# 08_Extention_GPIO.net
KiCad netlist of a schematic drawn in Altium Designer
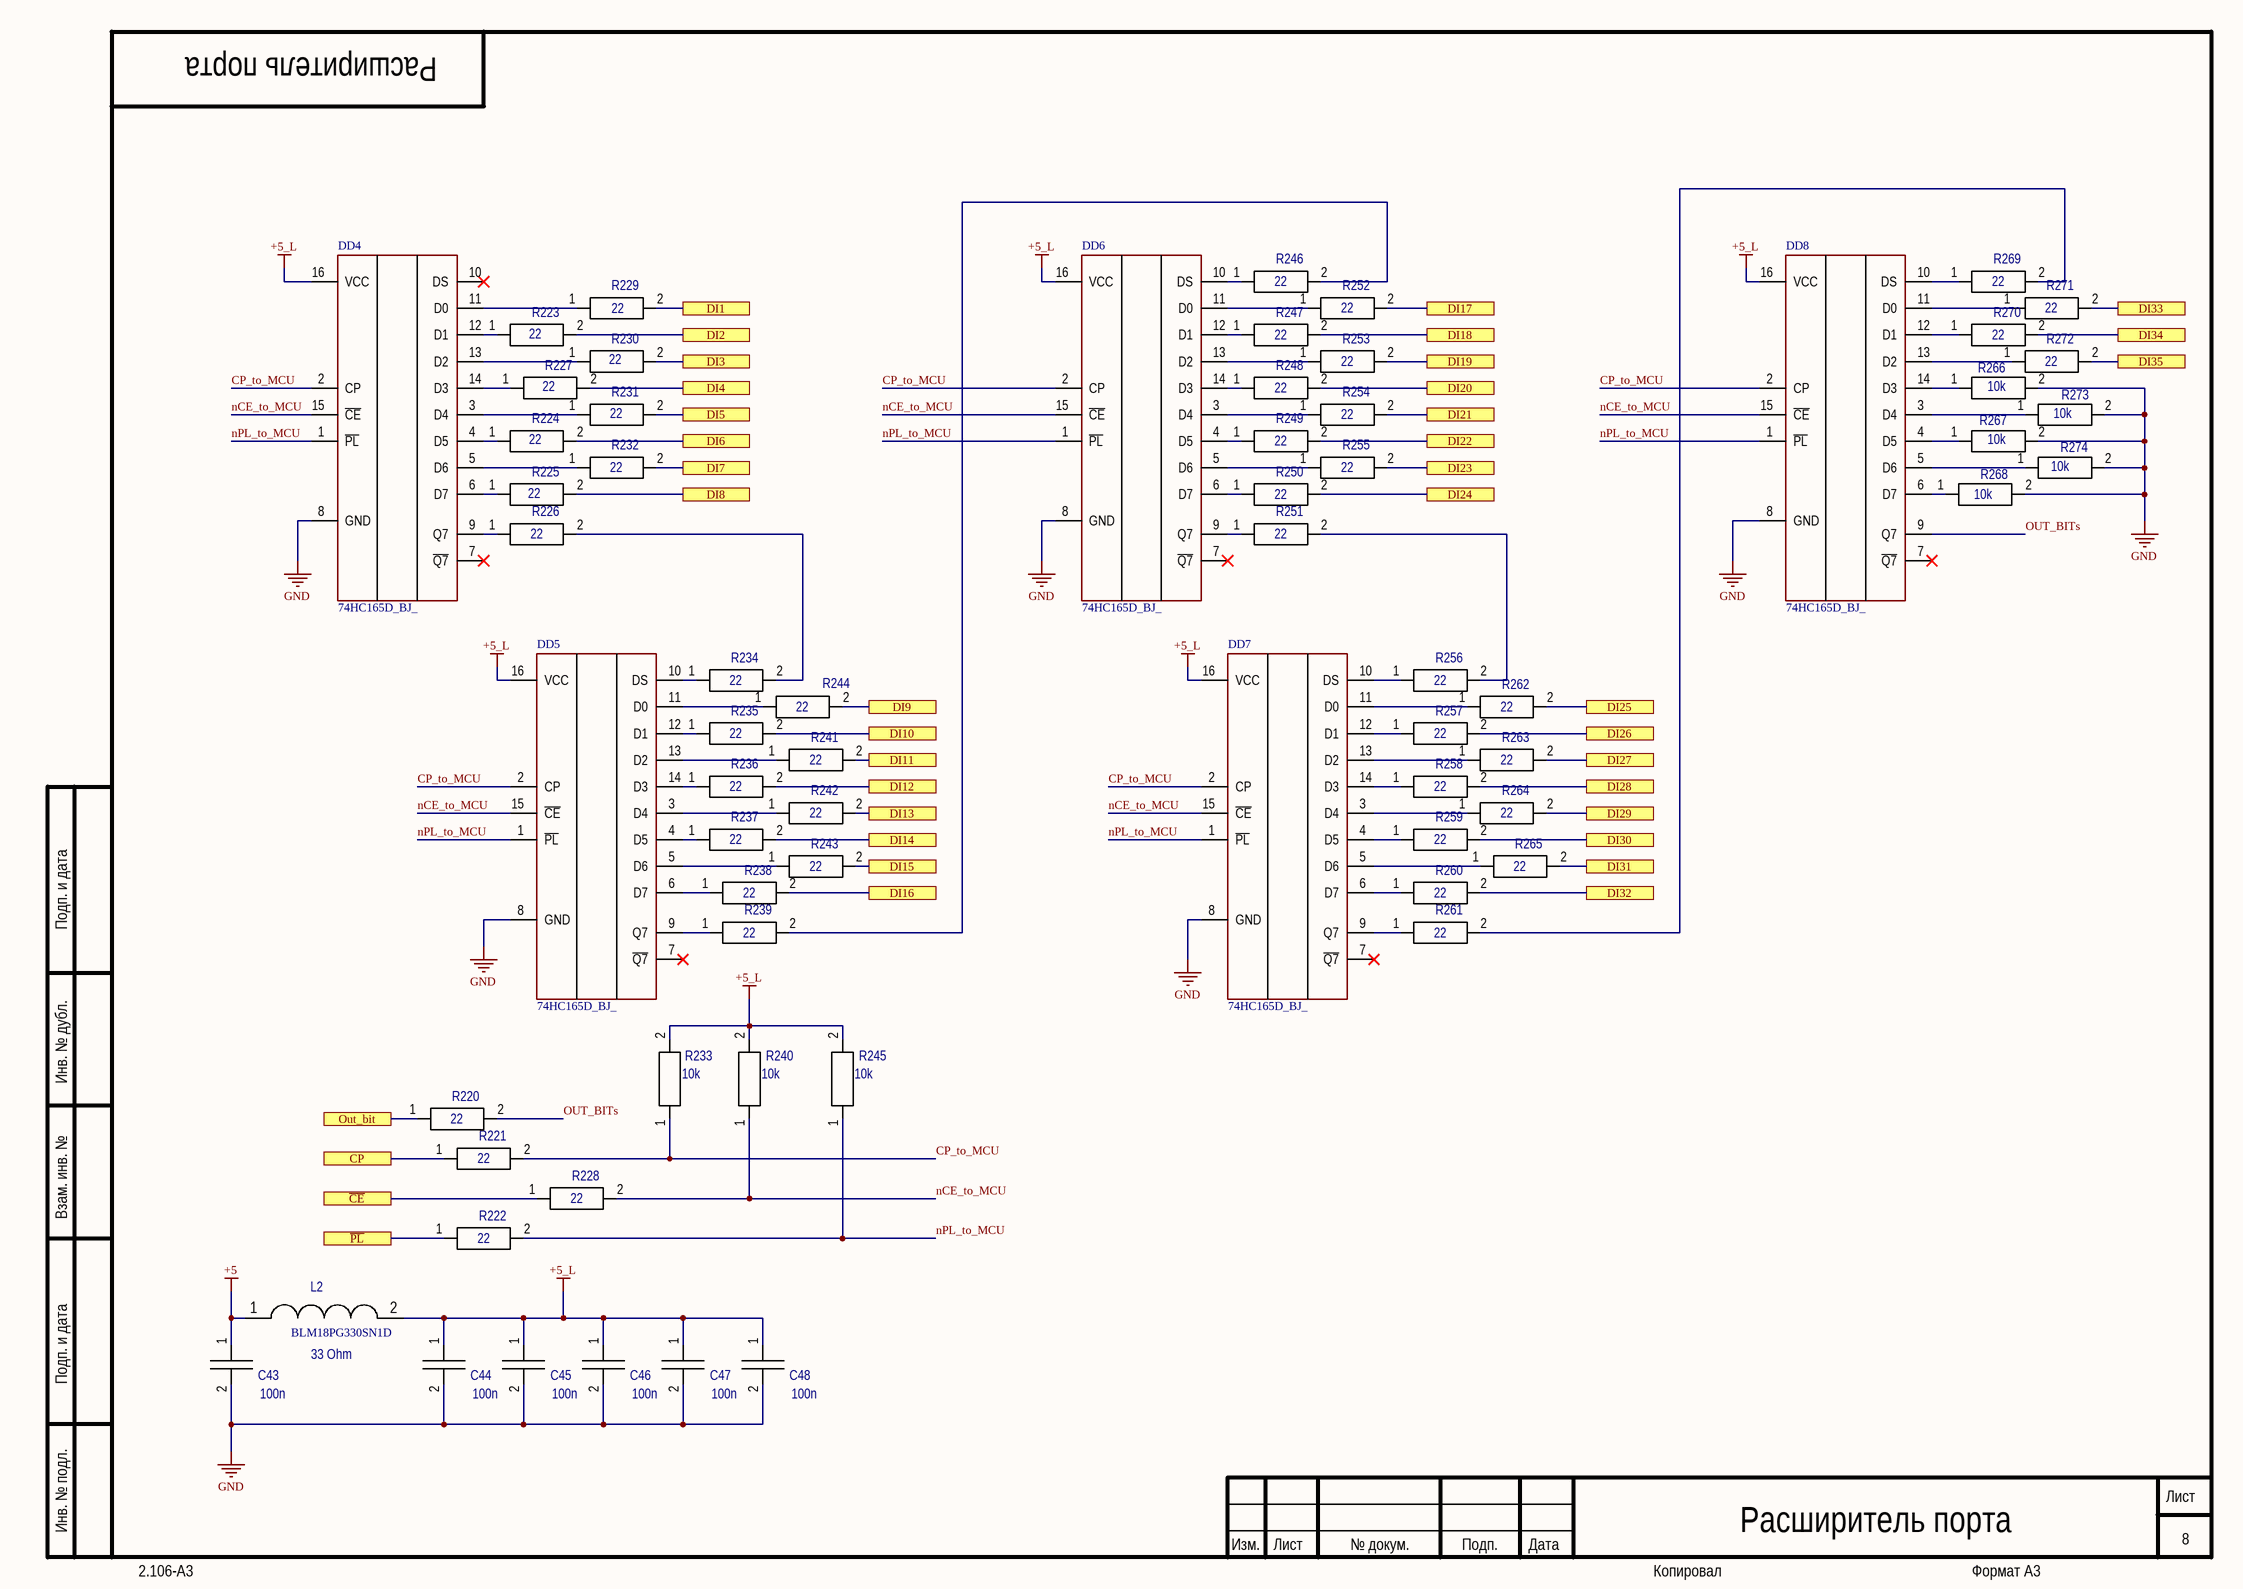
[diagram p0: 08_Extention_GPIO.SchDoc]

(export (version "E")
  (design (tool "Eeschema 10.0.6"))
  (components
    (comp (ref "C43")
      (value "100n")
      (footprint "C0603")
      (fields
        (field (name "PART NUMBER") "GRM188R71C104KA01D")
        (field (name "TOLERANCE") "±10%")
        (field (name "MANUFACTURER") "Murata Manufacturing")
      )
      (libsource (lib "AccessLibrary") (part "Capacitor"))
    )
    (comp (ref "C44")
      (value "100n")
      (footprint "C0603")
      (fields
        (field (name "PART NUMBER") "GRM188R71C104KA01D")
        (field (name "TOLERANCE") "±10%")
        (field (name "MANUFACTURER") "Murata Manufacturing")
      )
      (libsource (lib "AccessLibrary") (part "Capacitor"))
    )
    (comp (ref "C45")
      (value "100n")
      (footprint "C0603")
      (fields
        (field (name "PART NUMBER") "GRM188R71C104KA01D")
        (field (name "TOLERANCE") "±10%")
        (field (name "MANUFACTURER") "Murata Manufacturing")
      )
      (libsource (lib "AccessLibrary") (part "Capacitor"))
    )
    (comp (ref "C46")
      (value "100n")
      (footprint "C0603")
      (fields
        (field (name "PART NUMBER") "GRM188R71C104KA01D")
        (field (name "TOLERANCE") "±10%")
        (field (name "MANUFACTURER") "Murata Manufacturing")
      )
      (libsource (lib "AccessLibrary") (part "Capacitor"))
    )
    (comp (ref "C47")
      (value "100n")
      (footprint "C0603")
      (fields
        (field (name "PART NUMBER") "GRM188R71C104KA01D")
        (field (name "TOLERANCE") "±10%")
        (field (name "MANUFACTURER") "Murata Manufacturing")
      )
      (libsource (lib "AccessLibrary") (part "Capacitor"))
    )
    (comp (ref "C48")
      (value "100n")
      (footprint "C0603")
      (fields
        (field (name "PART NUMBER") "GRM188R71C104KA01D")
        (field (name "TOLERANCE") "±10%")
        (field (name "MANUFACTURER") "Murata Manufacturing")
      )
      (libsource (lib "AccessLibrary") (part "Capacitor"))
    )
    (comp (ref "DD4")
      (value "74HC165D_BJ_")
      (footprint "board:SOIC127P600X175-16N")
      (description "Integrated Circuit")
      (fields (field (name "PARTNUMBER") "74HC165D(BJ)") (field (name "MOUSER PART NUMBER") "757-74HC165DBJ"))
      (libsource (lib "board") (part "74HC165D_BJ_"))
    )
    (comp (ref "DD5")
      (value "74HC165D_BJ_")
      (footprint "board:SOIC127P600X175-16N")
      (description "Integrated Circuit")
      (fields (field (name "PARTNUMBER") "74HC165D(BJ)") (field (name "MOUSER PART NUMBER") "757-74HC165DBJ"))
      (libsource (lib "board") (part "74HC165D_BJ_"))
    )
    (comp (ref "DD6")
      (value "74HC165D_BJ_")
      (footprint "board:SOIC127P600X175-16N")
      (description "Integrated Circuit")
      (fields (field (name "PARTNUMBER") "74HC165D(BJ)") (field (name "MOUSER PART NUMBER") "757-74HC165DBJ"))
      (libsource (lib "board") (part "74HC165D_BJ_"))
    )
    (comp (ref "DD7")
      (value "74HC165D_BJ_")
      (footprint "board:SOIC127P600X175-16N")
      (description "Integrated Circuit")
      (fields (field (name "PARTNUMBER") "74HC165D(BJ)") (field (name "MOUSER PART NUMBER") "757-74HC165DBJ"))
      (libsource (lib "board") (part "74HC165D_BJ_"))
    )
    (comp (ref "DD8")
      (value "74HC165D_BJ_")
      (footprint "board:SOIC127P600X175-16N")
      (description "Integrated Circuit")
      (fields (field (name "PARTNUMBER") "74HC165D(BJ)") (field (name "MOUSER PART NUMBER") "757-74HC165DBJ"))
      (libsource (lib "board") (part "74HC165D_BJ_"))
    )
    (comp (ref "L2")
      (value "BLM18PG330SN1D")
      (footprint "INDC1608N")
      (fields (field (name "ALTIUM_VALUE") "33 Ohm"))
      (libsource (lib "AccessLibrary") (part "Inductance"))
    )
    (comp (ref "R220")
      (value "22")
      (footprint "RESC1608N")
      (fields
        (field (name "PART NUMBER") "RC0603FK-0722RL")
        (field (name "TOLERANCE") "±1%")
        (field (name "MANUFACTURER") "Тайвань")
      )
      (libsource (lib "AccessLibrary") (part "Resistor"))
    )
    (comp (ref "R221")
      (value "22")
      (footprint "RESC1608N")
      (fields
        (field (name "PART NUMBER") "RC0603FK-0722RL")
        (field (name "TOLERANCE") "±1%")
        (field (name "MANUFACTURER") "Тайвань")
      )
      (libsource (lib "AccessLibrary") (part "Resistor"))
    )
    (comp (ref "R222")
      (value "22")
      (footprint "RESC1608N")
      (fields
        (field (name "PART NUMBER") "RC0603FK-0722RL")
        (field (name "TOLERANCE") "±1%")
        (field (name "MANUFACTURER") "Тайвань")
      )
      (libsource (lib "AccessLibrary") (part "Resistor"))
    )
    (comp (ref "R223")
      (value "22")
      (footprint "RESC1608N")
      (fields
        (field (name "PART NUMBER") "RC0603FK-0722RL")
        (field (name "TOLERANCE") "±1%")
        (field (name "MANUFACTURER") "Тайвань")
      )
      (libsource (lib "AccessLibrary") (part "Resistor"))
    )
    (comp (ref "R224")
      (value "22")
      (footprint "RESC1608N")
      (fields
        (field (name "PART NUMBER") "RC0603FK-0722RL")
        (field (name "TOLERANCE") "±1%")
        (field (name "MANUFACTURER") "Тайвань")
      )
      (libsource (lib "AccessLibrary") (part "Resistor"))
    )
    (comp (ref "R225")
      (value "22")
      (footprint "RESC1608N")
      (fields
        (field (name "PART NUMBER") "RC0603FK-0722RL")
        (field (name "TOLERANCE") "±1%")
        (field (name "MANUFACTURER") "Тайвань")
      )
      (libsource (lib "AccessLibrary") (part "Resistor"))
    )
    (comp (ref "R226")
      (value "22")
      (footprint "RESC1608N")
      (fields
        (field (name "PART NUMBER") "RC0603FK-0722RL")
        (field (name "TOLERANCE") "±1%")
        (field (name "MANUFACTURER") "Тайвань")
      )
      (libsource (lib "AccessLibrary") (part "Resistor"))
    )
    (comp (ref "R227")
      (value "22")
      (footprint "RESC1608N")
      (fields
        (field (name "PART NUMBER") "RC0603FK-0722RL")
        (field (name "TOLERANCE") "±1%")
        (field (name "MANUFACTURER") "Тайвань")
      )
      (libsource (lib "AccessLibrary") (part "Resistor"))
    )
    (comp (ref "R228")
      (value "22")
      (footprint "RESC1608N")
      (fields
        (field (name "PART NUMBER") "RC0603FK-0722RL")
        (field (name "TOLERANCE") "±1%")
        (field (name "MANUFACTURER") "Тайвань")
      )
      (libsource (lib "AccessLibrary") (part "Resistor"))
    )
    (comp (ref "R229")
      (value "22")
      (footprint "RESC1608N")
      (fields
        (field (name "PART NUMBER") "RC0603FK-0722RL")
        (field (name "TOLERANCE") "±1%")
        (field (name "MANUFACTURER") "Тайвань")
      )
      (libsource (lib "AccessLibrary") (part "Resistor"))
    )
    (comp (ref "R230")
      (value "22")
      (footprint "RESC1608N")
      (fields
        (field (name "PART NUMBER") "RC0603FK-0722RL")
        (field (name "TOLERANCE") "±1%")
        (field (name "MANUFACTURER") "Тайвань")
      )
      (libsource (lib "AccessLibrary") (part "Resistor"))
    )
    (comp (ref "R231")
      (value "22")
      (footprint "RESC1608N")
      (fields
        (field (name "PART NUMBER") "RC0603FK-0722RL")
        (field (name "TOLERANCE") "±1%")
        (field (name "MANUFACTURER") "Тайвань")
      )
      (libsource (lib "AccessLibrary") (part "Resistor"))
    )
    (comp (ref "R232")
      (value "22")
      (footprint "RESC1608N")
      (fields
        (field (name "PART NUMBER") "RC0603FK-0722RL")
        (field (name "TOLERANCE") "±1%")
        (field (name "MANUFACTURER") "Тайвань")
      )
      (libsource (lib "AccessLibrary") (part "Resistor"))
    )
    (comp (ref "R233")
      (value "10k")
      (footprint "RESC1608N")
      (fields
        (field (name "PART NUMBER") "RC0603FR-0710KL")
        (field (name "TOLERANCE") "±1%")
        (field (name "MANUFACTURER") "Тайвань")
      )
      (libsource (lib "AccessLibrary") (part "Resistor"))
    )
    (comp (ref "R234")
      (value "22")
      (footprint "RESC1608N")
      (fields
        (field (name "PART NUMBER") "RC0603FK-0722RL")
        (field (name "TOLERANCE") "±1%")
        (field (name "MANUFACTURER") "Тайвань")
      )
      (libsource (lib "AccessLibrary") (part "Resistor"))
    )
    (comp (ref "R235")
      (value "22")
      (footprint "RESC1608N")
      (fields
        (field (name "PART NUMBER") "RC0603FK-0722RL")
        (field (name "TOLERANCE") "±1%")
        (field (name "MANUFACTURER") "Тайвань")
      )
      (libsource (lib "AccessLibrary") (part "Resistor"))
    )
    (comp (ref "R236")
      (value "22")
      (footprint "RESC1608N")
      (fields
        (field (name "PART NUMBER") "RC0603FK-0722RL")
        (field (name "TOLERANCE") "±1%")
        (field (name "MANUFACTURER") "Тайвань")
      )
      (libsource (lib "AccessLibrary") (part "Resistor"))
    )
    (comp (ref "R237")
      (value "22")
      (footprint "RESC1608N")
      (fields
        (field (name "PART NUMBER") "RC0603FK-0722RL")
        (field (name "TOLERANCE") "±1%")
        (field (name "MANUFACTURER") "Тайвань")
      )
      (libsource (lib "AccessLibrary") (part "Resistor"))
    )
    (comp (ref "R238")
      (value "22")
      (footprint "RESC1608N")
      (fields
        (field (name "PART NUMBER") "RC0603FK-0722RL")
        (field (name "TOLERANCE") "±1%")
        (field (name "MANUFACTURER") "Тайвань")
      )
      (libsource (lib "AccessLibrary") (part "Resistor"))
    )
    (comp (ref "R239")
      (value "22")
      (footprint "RESC1608N")
      (fields
        (field (name "PART NUMBER") "RC0603FK-0722RL")
        (field (name "TOLERANCE") "±1%")
        (field (name "MANUFACTURER") "Тайвань")
      )
      (libsource (lib "AccessLibrary") (part "Resistor"))
    )
    (comp (ref "R240")
      (value "10k")
      (footprint "RESC1608N")
      (fields
        (field (name "PART NUMBER") "RC0603FR-0710KL")
        (field (name "TOLERANCE") "±1%")
        (field (name "MANUFACTURER") "Тайвань")
      )
      (libsource (lib "AccessLibrary") (part "Resistor"))
    )
    (comp (ref "R241")
      (value "22")
      (footprint "RESC1608N")
      (fields
        (field (name "PART NUMBER") "RC0603FK-0722RL")
        (field (name "TOLERANCE") "±1%")
        (field (name "MANUFACTURER") "Тайвань")
      )
      (libsource (lib "AccessLibrary") (part "Resistor"))
    )
    (comp (ref "R242")
      (value "22")
      (footprint "RESC1608N")
      (fields
        (field (name "PART NUMBER") "RC0603FK-0722RL")
        (field (name "TOLERANCE") "±1%")
        (field (name "MANUFACTURER") "Тайвань")
      )
      (libsource (lib "AccessLibrary") (part "Resistor"))
    )
    (comp (ref "R243")
      (value "22")
      (footprint "RESC1608N")
      (fields
        (field (name "PART NUMBER") "RC0603FK-0722RL")
        (field (name "TOLERANCE") "±1%")
        (field (name "MANUFACTURER") "Тайвань")
      )
      (libsource (lib "AccessLibrary") (part "Resistor"))
    )
    (comp (ref "R244")
      (value "22")
      (footprint "RESC1608N")
      (fields
        (field (name "PART NUMBER") "RC0603FK-0722RL")
        (field (name "TOLERANCE") "±1%")
        (field (name "MANUFACTURER") "Тайвань")
      )
      (libsource (lib "AccessLibrary") (part "Resistor"))
    )
    (comp (ref "R245")
      (value "10k")
      (footprint "RESC1608N")
      (fields
        (field (name "PART NUMBER") "RC0603FR-0710KL")
        (field (name "TOLERANCE") "±1%")
        (field (name "MANUFACTURER") "Тайвань")
      )
      (libsource (lib "AccessLibrary") (part "Resistor"))
    )
    (comp (ref "R246")
      (value "22")
      (footprint "RESC1608N")
      (fields
        (field (name "PART NUMBER") "RC0603FK-0722RL")
        (field (name "TOLERANCE") "±1%")
        (field (name "MANUFACTURER") "Тайвань")
      )
      (libsource (lib "AccessLibrary") (part "Resistor"))
    )
    (comp (ref "R247")
      (value "22")
      (footprint "RESC1608N")
      (fields
        (field (name "PART NUMBER") "RC0603FK-0722RL")
        (field (name "TOLERANCE") "±1%")
        (field (name "MANUFACTURER") "Тайвань")
      )
      (libsource (lib "AccessLibrary") (part "Resistor"))
    )
    (comp (ref "R248")
      (value "22")
      (footprint "RESC1608N")
      (fields
        (field (name "PART NUMBER") "RC0603FK-0722RL")
        (field (name "TOLERANCE") "±1%")
        (field (name "MANUFACTURER") "Тайвань")
      )
      (libsource (lib "AccessLibrary") (part "Resistor"))
    )
    (comp (ref "R249")
      (value "22")
      (footprint "RESC1608N")
      (fields
        (field (name "PART NUMBER") "RC0603FK-0722RL")
        (field (name "TOLERANCE") "±1%")
        (field (name "MANUFACTURER") "Тайвань")
      )
      (libsource (lib "AccessLibrary") (part "Resistor"))
    )
    (comp (ref "R250")
      (value "22")
      (footprint "RESC1608N")
      (fields
        (field (name "PART NUMBER") "RC0603FK-0722RL")
        (field (name "TOLERANCE") "±1%")
        (field (name "MANUFACTURER") "Тайвань")
      )
      (libsource (lib "AccessLibrary") (part "Resistor"))
    )
    (comp (ref "R251")
      (value "22")
      (footprint "RESC1608N")
      (fields
        (field (name "PART NUMBER") "RC0603FK-0722RL")
        (field (name "TOLERANCE") "±1%")
        (field (name "MANUFACTURER") "Тайвань")
      )
      (libsource (lib "AccessLibrary") (part "Resistor"))
    )
    (comp (ref "R252")
      (value "22")
      (footprint "RESC1608N")
      (fields
        (field (name "PART NUMBER") "RC0603FK-0722RL")
        (field (name "TOLERANCE") "±1%")
        (field (name "MANUFACTURER") "Тайвань")
      )
      (libsource (lib "AccessLibrary") (part "Resistor"))
    )
    (comp (ref "R253")
      (value "22")
      (footprint "RESC1608N")
      (fields
        (field (name "PART NUMBER") "RC0603FK-0722RL")
        (field (name "TOLERANCE") "±1%")
        (field (name "MANUFACTURER") "Тайвань")
      )
      (libsource (lib "AccessLibrary") (part "Resistor"))
    )
    (comp (ref "R254")
      (value "22")
      (footprint "RESC1608N")
      (fields
        (field (name "PART NUMBER") "RC0603FK-0722RL")
        (field (name "TOLERANCE") "±1%")
        (field (name "MANUFACTURER") "Тайвань")
      )
      (libsource (lib "AccessLibrary") (part "Resistor"))
    )
    (comp (ref "R255")
      (value "22")
      (footprint "RESC1608N")
      (fields
        (field (name "PART NUMBER") "RC0603FK-0722RL")
        (field (name "TOLERANCE") "±1%")
        (field (name "MANUFACTURER") "Тайвань")
      )
      (libsource (lib "AccessLibrary") (part "Resistor"))
    )
    (comp (ref "R256")
      (value "22")
      (footprint "RESC1608N")
      (fields
        (field (name "PART NUMBER") "RC0603FK-0722RL")
        (field (name "TOLERANCE") "±1%")
        (field (name "MANUFACTURER") "Тайвань")
      )
      (libsource (lib "AccessLibrary") (part "Resistor"))
    )
    (comp (ref "R257")
      (value "22")
      (footprint "RESC1608N")
      (fields
        (field (name "PART NUMBER") "RC0603FK-0722RL")
        (field (name "TOLERANCE") "±1%")
        (field (name "MANUFACTURER") "Тайвань")
      )
      (libsource (lib "AccessLibrary") (part "Resistor"))
    )
    (comp (ref "R258")
      (value "22")
      (footprint "RESC1608N")
      (fields
        (field (name "PART NUMBER") "RC0603FK-0722RL")
        (field (name "TOLERANCE") "±1%")
        (field (name "MANUFACTURER") "Тайвань")
      )
      (libsource (lib "AccessLibrary") (part "Resistor"))
    )
    (comp (ref "R259")
      (value "22")
      (footprint "RESC1608N")
      (fields
        (field (name "PART NUMBER") "RC0603FK-0722RL")
        (field (name "TOLERANCE") "±1%")
        (field (name "MANUFACTURER") "Тайвань")
      )
      (libsource (lib "AccessLibrary") (part "Resistor"))
    )
    (comp (ref "R260")
      (value "22")
      (footprint "RESC1608N")
      (fields
        (field (name "PART NUMBER") "RC0603FK-0722RL")
        (field (name "TOLERANCE") "±1%")
        (field (name "MANUFACTURER") "Тайвань")
      )
      (libsource (lib "AccessLibrary") (part "Resistor"))
    )
    (comp (ref "R261")
      (value "22")
      (footprint "RESC1608N")
      (fields
        (field (name "PART NUMBER") "RC0603FK-0722RL")
        (field (name "TOLERANCE") "±1%")
        (field (name "MANUFACTURER") "Тайвань")
      )
      (libsource (lib "AccessLibrary") (part "Resistor"))
    )
    (comp (ref "R262")
      (value "22")
      (footprint "RESC1608N")
      (fields
        (field (name "PART NUMBER") "RC0603FK-0722RL")
        (field (name "TOLERANCE") "±1%")
        (field (name "MANUFACTURER") "Тайвань")
      )
      (libsource (lib "AccessLibrary") (part "Resistor"))
    )
    (comp (ref "R263")
      (value "22")
      (footprint "RESC1608N")
      (fields
        (field (name "PART NUMBER") "RC0603FK-0722RL")
        (field (name "TOLERANCE") "±1%")
        (field (name "MANUFACTURER") "Тайвань")
      )
      (libsource (lib "AccessLibrary") (part "Resistor"))
    )
    (comp (ref "R264")
      (value "22")
      (footprint "RESC1608N")
      (fields
        (field (name "PART NUMBER") "RC0603FK-0722RL")
        (field (name "TOLERANCE") "±1%")
        (field (name "MANUFACTURER") "Тайвань")
      )
      (libsource (lib "AccessLibrary") (part "Resistor"))
    )
    (comp (ref "R265")
      (value "22")
      (footprint "RESC1608N")
      (fields
        (field (name "PART NUMBER") "RC0603FK-0722RL")
        (field (name "TOLERANCE") "±1%")
        (field (name "MANUFACTURER") "Тайвань")
      )
      (libsource (lib "AccessLibrary") (part "Resistor"))
    )
    (comp (ref "R266")
      (value "10k")
      (footprint "RESC1608N")
      (fields
        (field (name "PART NUMBER") "RC0603FR-0710KL")
        (field (name "TOLERANCE") "±1%")
        (field (name "MANUFACTURER") "Тайвань")
      )
      (libsource (lib "AccessLibrary") (part "Resistor"))
    )
    (comp (ref "R267")
      (value "10k")
      (footprint "RESC1608N")
      (fields
        (field (name "PART NUMBER") "RC0603FR-0710KL")
        (field (name "TOLERANCE") "±1%")
        (field (name "MANUFACTURER") "Тайвань")
      )
      (libsource (lib "AccessLibrary") (part "Resistor"))
    )
    (comp (ref "R268")
      (value "10k")
      (footprint "RESC1608N")
      (fields
        (field (name "PART NUMBER") "RC0603FR-0710KL")
        (field (name "TOLERANCE") "±1%")
        (field (name "MANUFACTURER") "Тайвань")
      )
      (libsource (lib "AccessLibrary") (part "Resistor"))
    )
    (comp (ref "R269")
      (value "22")
      (footprint "RESC1608N")
      (fields
        (field (name "PART NUMBER") "RC0603FK-0722RL")
        (field (name "TOLERANCE") "±1%")
        (field (name "MANUFACTURER") "Тайвань")
      )
      (libsource (lib "AccessLibrary") (part "Resistor"))
    )
    (comp (ref "R270")
      (value "22")
      (footprint "RESC1608N")
      (fields
        (field (name "PART NUMBER") "RC0603FK-0722RL")
        (field (name "TOLERANCE") "±1%")
        (field (name "MANUFACTURER") "Тайвань")
      )
      (libsource (lib "AccessLibrary") (part "Resistor"))
    )
    (comp (ref "R271")
      (value "22")
      (footprint "RESC1608N")
      (fields
        (field (name "PART NUMBER") "RC0603FK-0722RL")
        (field (name "TOLERANCE") "±1%")
        (field (name "MANUFACTURER") "Тайвань")
      )
      (libsource (lib "AccessLibrary") (part "Resistor"))
    )
    (comp (ref "R272")
      (value "22")
      (footprint "RESC1608N")
      (fields
        (field (name "PART NUMBER") "RC0603FK-0722RL")
        (field (name "TOLERANCE") "±1%")
        (field (name "MANUFACTURER") "Тайвань")
      )
      (libsource (lib "AccessLibrary") (part "Resistor"))
    )
    (comp (ref "R273")
      (value "10k")
      (footprint "RESC1608N")
      (fields
        (field (name "PART NUMBER") "RC0603FR-0710KL")
        (field (name "TOLERANCE") "±1%")
        (field (name "MANUFACTURER") "Тайвань")
      )
      (libsource (lib "AccessLibrary") (part "Resistor"))
    )
    (comp (ref "R274")
      (value "10k")
      (footprint "RESC1608N")
      (fields
        (field (name "PART NUMBER") "RC0603FR-0710KL")
        (field (name "TOLERANCE") "±1%")
        (field (name "MANUFACTURER") "Тайвань")
      )
      (libsource (lib "AccessLibrary") (part "Resistor"))
    )
  )
  (nets
    (net (code "1") (name "+5") (class "Default")
      (node (ref "C43") (pin "1") (pinfunction "1_1") (pintype "passive"))
      (node (ref "L2") (pin "1") (pinfunction "1_1") (pintype "passive"))
    )
    (net (code "2") (name "+5_L") (class "Default")
      (node (ref "C44") (pin "1") (pinfunction "1_1") (pintype "passive"))
      (node (ref "C45") (pin "1") (pinfunction "1_1") (pintype "passive"))
      (node (ref "C46") (pin "1") (pinfunction "1_1") (pintype "passive"))
      (node (ref "C47") (pin "1") (pinfunction "1_1") (pintype "passive"))
      (node (ref "C48") (pin "1") (pinfunction "1_1") (pintype "passive"))
      (node (ref "DD4") (pin "16") (pinfunction "VCC_16") (pintype "passive"))
      (node (ref "DD5") (pin "16") (pinfunction "VCC_16") (pintype "passive"))
      (node (ref "DD6") (pin "16") (pinfunction "VCC_16") (pintype "passive"))
      (node (ref "DD7") (pin "16") (pinfunction "VCC_16") (pintype "passive"))
      (node (ref "DD8") (pin "16") (pinfunction "VCC_16") (pintype "passive"))
      (node (ref "L2") (pin "2") (pinfunction "2_2") (pintype "passive"))
      (node (ref "R233") (pin "2") (pinfunction "2_2") (pintype "passive"))
      (node (ref "R240") (pin "2") (pinfunction "2_2") (pintype "passive"))
      (node (ref "R245") (pin "2") (pinfunction "2_2") (pintype "passive"))
    )
    (net (code "3") (name "/CP") (class "Default")
      (node (ref "R221") (pin "1") (pinfunction "1_1") (pintype "passive"))
    )
    (net (code "4") (name "/CP_to_MCU") (class "Default")
      (node (ref "DD4") (pin "2") (pinfunction "CP_2") (pintype "passive"))
      (node (ref "DD5") (pin "2") (pinfunction "CP_2") (pintype "passive"))
      (node (ref "DD6") (pin "2") (pinfunction "CP_2") (pintype "passive"))
      (node (ref "DD7") (pin "2") (pinfunction "CP_2") (pintype "passive"))
      (node (ref "DD8") (pin "2") (pinfunction "CP_2") (pintype "passive"))
      (node (ref "R221") (pin "2") (pinfunction "2_2") (pintype "passive"))
      (node (ref "R233") (pin "1") (pinfunction "1_1") (pintype "passive"))
    )
    (net (code "5") (name "/DI1") (class "Default")
      (node (ref "R229") (pin "2") (pinfunction "2_2") (pintype "passive"))
    )
    (net (code "6") (name "/DI2") (class "Default")
      (node (ref "R223") (pin "2") (pinfunction "2_2") (pintype "passive"))
    )
    (net (code "7") (name "/DI3") (class "Default")
      (node (ref "R230") (pin "2") (pinfunction "2_2") (pintype "passive"))
    )
    (net (code "8") (name "/DI4") (class "Default")
      (node (ref "R227") (pin "2") (pinfunction "2_2") (pintype "passive"))
    )
    (net (code "9") (name "/DI5") (class "Default")
      (node (ref "R231") (pin "2") (pinfunction "2_2") (pintype "passive"))
    )
    (net (code "10") (name "/DI6") (class "Default")
      (node (ref "R224") (pin "2") (pinfunction "2_2") (pintype "passive"))
    )
    (net (code "11") (name "/DI7") (class "Default")
      (node (ref "R232") (pin "2") (pinfunction "2_2") (pintype "passive"))
    )
    (net (code "12") (name "/DI8") (class "Default")
      (node (ref "R225") (pin "2") (pinfunction "2_2") (pintype "passive"))
    )
    (net (code "13") (name "/DI9") (class "Default")
      (node (ref "R244") (pin "2") (pinfunction "2_2") (pintype "passive"))
    )
    (net (code "14") (name "/DI10") (class "Default")
      (node (ref "R235") (pin "2") (pinfunction "2_2") (pintype "passive"))
    )
    (net (code "15") (name "/DI11") (class "Default")
      (node (ref "R241") (pin "2") (pinfunction "2_2") (pintype "passive"))
    )
    (net (code "16") (name "/DI12") (class "Default")
      (node (ref "R236") (pin "2") (pinfunction "2_2") (pintype "passive"))
    )
    (net (code "17") (name "/DI13") (class "Default")
      (node (ref "R242") (pin "2") (pinfunction "2_2") (pintype "passive"))
    )
    (net (code "18") (name "/DI14") (class "Default")
      (node (ref "R237") (pin "2") (pinfunction "2_2") (pintype "passive"))
    )
    (net (code "19") (name "/DI15") (class "Default")
      (node (ref "R243") (pin "2") (pinfunction "2_2") (pintype "passive"))
    )
    (net (code "20") (name "/DI16") (class "Default")
      (node (ref "R238") (pin "2") (pinfunction "2_2") (pintype "passive"))
    )
    (net (code "21") (name "/DI17") (class "Default")
      (node (ref "R252") (pin "2") (pinfunction "2_2") (pintype "passive"))
    )
    (net (code "22") (name "/DI18") (class "Default")
      (node (ref "R247") (pin "2") (pinfunction "2_2") (pintype "passive"))
    )
    (net (code "23") (name "/DI19") (class "Default")
      (node (ref "R253") (pin "2") (pinfunction "2_2") (pintype "passive"))
    )
    (net (code "24") (name "/DI20") (class "Default")
      (node (ref "R248") (pin "2") (pinfunction "2_2") (pintype "passive"))
    )
    (net (code "25") (name "/DI21") (class "Default")
      (node (ref "R254") (pin "2") (pinfunction "2_2") (pintype "passive"))
    )
    (net (code "26") (name "/DI22") (class "Default")
      (node (ref "R249") (pin "2") (pinfunction "2_2") (pintype "passive"))
    )
    (net (code "27") (name "/DI23") (class "Default")
      (node (ref "R255") (pin "2") (pinfunction "2_2") (pintype "passive"))
    )
    (net (code "28") (name "/DI24") (class "Default")
      (node (ref "R250") (pin "2") (pinfunction "2_2") (pintype "passive"))
    )
    (net (code "29") (name "/DI25") (class "Default")
      (node (ref "R262") (pin "2") (pinfunction "2_2") (pintype "passive"))
    )
    (net (code "30") (name "/DI26") (class "Default")
      (node (ref "R257") (pin "2") (pinfunction "2_2") (pintype "passive"))
    )
    (net (code "31") (name "/DI27") (class "Default")
      (node (ref "R263") (pin "2") (pinfunction "2_2") (pintype "passive"))
    )
    (net (code "32") (name "/DI28") (class "Default")
      (node (ref "R258") (pin "2") (pinfunction "2_2") (pintype "passive"))
    )
    (net (code "33") (name "/DI29") (class "Default")
      (node (ref "R264") (pin "2") (pinfunction "2_2") (pintype "passive"))
    )
    (net (code "34") (name "/DI30") (class "Default")
      (node (ref "R259") (pin "2") (pinfunction "2_2") (pintype "passive"))
    )
    (net (code "35") (name "/DI31") (class "Default")
      (node (ref "R265") (pin "2") (pinfunction "2_2") (pintype "passive"))
    )
    (net (code "36") (name "/DI32") (class "Default")
      (node (ref "R260") (pin "2") (pinfunction "2_2") (pintype "passive"))
    )
    (net (code "37") (name "/DI33") (class "Default")
      (node (ref "R271") (pin "2") (pinfunction "2_2") (pintype "passive"))
    )
    (net (code "38") (name "/DI34") (class "Default")
      (node (ref "R270") (pin "2") (pinfunction "2_2") (pintype "passive"))
    )
    (net (code "39") (name "/DI35") (class "Default")
      (node (ref "R272") (pin "2") (pinfunction "2_2") (pintype "passive"))
    )
    (net (code "40") (name "/OUT_BITs") (class "Default")
      (node (ref "DD8") (pin "9") (pinfunction "Q7_9") (pintype "passive"))
      (node (ref "R220") (pin "2") (pinfunction "2_2") (pintype "passive"))
    )
    (net (code "41") (name "/Out_bit") (class "Default")
      (node (ref "R220") (pin "1") (pinfunction "1_1") (pintype "passive"))
    )
    (net (code "42") (name "/nCE_to_MCU") (class "Default")
      (node (ref "DD4") (pin "15") (pinfunction "~{CE}_15") (pintype "passive"))
      (node (ref "DD5") (pin "15") (pinfunction "~{CE}_15") (pintype "passive"))
      (node (ref "DD6") (pin "15") (pinfunction "~{CE}_15") (pintype "passive"))
      (node (ref "DD7") (pin "15") (pinfunction "~{CE}_15") (pintype "passive"))
      (node (ref "DD8") (pin "15") (pinfunction "~{CE}_15") (pintype "passive"))
      (node (ref "R228") (pin "2") (pinfunction "2_2") (pintype "passive"))
      (node (ref "R240") (pin "1") (pinfunction "1_1") (pintype "passive"))
    )
    (net (code "43") (name "/nPL_to_MCU") (class "Default")
      (node (ref "DD4") (pin "1") (pinfunction "~{PL}_1") (pintype "passive"))
      (node (ref "DD5") (pin "1") (pinfunction "~{PL}_1") (pintype "passive"))
      (node (ref "DD6") (pin "1") (pinfunction "~{PL}_1") (pintype "passive"))
      (node (ref "DD7") (pin "1") (pinfunction "~{PL}_1") (pintype "passive"))
      (node (ref "DD8") (pin "1") (pinfunction "~{PL}_1") (pintype "passive"))
      (node (ref "R222") (pin "2") (pinfunction "2_2") (pintype "passive"))
      (node (ref "R245") (pin "1") (pinfunction "1_1") (pintype "passive"))
    )
    (net (code "44") (name "/~{CE}") (class "Default")
      (node (ref "R228") (pin "1") (pinfunction "1_1") (pintype "passive"))
    )
    (net (code "45") (name "/~{PL}") (class "Default")
      (node (ref "R222") (pin "1") (pinfunction "1_1") (pintype "passive"))
    )
    (net (code "46") (name "GND") (class "Default")
      (node (ref "C43") (pin "2") (pinfunction "2_2") (pintype "passive"))
      (node (ref "C44") (pin "2") (pinfunction "2_2") (pintype "passive"))
      (node (ref "C45") (pin "2") (pinfunction "2_2") (pintype "passive"))
      (node (ref "C46") (pin "2") (pinfunction "2_2") (pintype "passive"))
      (node (ref "C47") (pin "2") (pinfunction "2_2") (pintype "passive"))
      (node (ref "C48") (pin "2") (pinfunction "2_2") (pintype "passive"))
      (node (ref "DD4") (pin "8") (pinfunction "GND_8") (pintype "passive"))
      (node (ref "DD5") (pin "8") (pinfunction "GND_8") (pintype "passive"))
      (node (ref "DD6") (pin "8") (pinfunction "GND_8") (pintype "passive"))
      (node (ref "DD7") (pin "8") (pinfunction "GND_8") (pintype "passive"))
      (node (ref "DD8") (pin "8") (pinfunction "GND_8") (pintype "passive"))
      (node (ref "R266") (pin "2") (pinfunction "2_2") (pintype "passive"))
      (node (ref "R267") (pin "2") (pinfunction "2_2") (pintype "passive"))
      (node (ref "R268") (pin "2") (pinfunction "2_2") (pintype "passive"))
      (node (ref "R273") (pin "2") (pinfunction "2_2") (pintype "passive"))
      (node (ref "R274") (pin "2") (pinfunction "2_2") (pintype "passive"))
    )
    (net (code "47") (name "Net-(DD4-D0)") (class "Default")
      (node (ref "DD4") (pin "11") (pinfunction "D0_11") (pintype "passive"))
      (node (ref "R229") (pin "1") (pinfunction "1_1") (pintype "passive"))
    )
    (net (code "48") (name "Net-(DD4-D1)") (class "Default")
      (node (ref "DD4") (pin "12") (pinfunction "D1_12") (pintype "passive"))
      (node (ref "R223") (pin "1") (pinfunction "1_1") (pintype "passive"))
    )
    (net (code "49") (name "Net-(DD4-D2)") (class "Default")
      (node (ref "DD4") (pin "13") (pinfunction "D2_13") (pintype "passive"))
      (node (ref "R230") (pin "1") (pinfunction "1_1") (pintype "passive"))
    )
    (net (code "50") (name "Net-(DD4-D3)") (class "Default")
      (node (ref "DD4") (pin "14") (pinfunction "D3_14") (pintype "passive"))
      (node (ref "R227") (pin "1") (pinfunction "1_1") (pintype "passive"))
    )
    (net (code "51") (name "Net-(DD4-D4)") (class "Default")
      (node (ref "DD4") (pin "3") (pinfunction "D4_3") (pintype "passive"))
      (node (ref "R231") (pin "1") (pinfunction "1_1") (pintype "passive"))
    )
    (net (code "52") (name "Net-(DD4-D5)") (class "Default")
      (node (ref "DD4") (pin "4") (pinfunction "D5_4") (pintype "passive"))
      (node (ref "R224") (pin "1") (pinfunction "1_1") (pintype "passive"))
    )
    (net (code "53") (name "Net-(DD4-D6)") (class "Default")
      (node (ref "DD4") (pin "5") (pinfunction "D6_5") (pintype "passive"))
      (node (ref "R232") (pin "1") (pinfunction "1_1") (pintype "passive"))
    )
    (net (code "54") (name "Net-(DD4-D7)") (class "Default")
      (node (ref "DD4") (pin "6") (pinfunction "D7_6") (pintype "passive"))
      (node (ref "R225") (pin "1") (pinfunction "1_1") (pintype "passive"))
    )
    (net (code "55") (name "Net-(DD4-Q7)") (class "Default")
      (node (ref "DD4") (pin "9") (pinfunction "Q7_9") (pintype "passive"))
      (node (ref "R226") (pin "1") (pinfunction "1_1") (pintype "passive"))
    )
    (net (code "56") (name "Net-(DD5-D0)") (class "Default")
      (node (ref "DD5") (pin "11") (pinfunction "D0_11") (pintype "passive"))
      (node (ref "R244") (pin "1") (pinfunction "1_1") (pintype "passive"))
    )
    (net (code "57") (name "Net-(DD5-D1)") (class "Default")
      (node (ref "DD5") (pin "12") (pinfunction "D1_12") (pintype "passive"))
      (node (ref "R235") (pin "1") (pinfunction "1_1") (pintype "passive"))
    )
    (net (code "58") (name "Net-(DD5-D2)") (class "Default")
      (node (ref "DD5") (pin "13") (pinfunction "D2_13") (pintype "passive"))
      (node (ref "R241") (pin "1") (pinfunction "1_1") (pintype "passive"))
    )
    (net (code "59") (name "Net-(DD5-D3)") (class "Default")
      (node (ref "DD5") (pin "14") (pinfunction "D3_14") (pintype "passive"))
      (node (ref "R236") (pin "1") (pinfunction "1_1") (pintype "passive"))
    )
    (net (code "60") (name "Net-(DD5-D4)") (class "Default")
      (node (ref "DD5") (pin "3") (pinfunction "D4_3") (pintype "passive"))
      (node (ref "R242") (pin "1") (pinfunction "1_1") (pintype "passive"))
    )
    (net (code "61") (name "Net-(DD5-D5)") (class "Default")
      (node (ref "DD5") (pin "4") (pinfunction "D5_4") (pintype "passive"))
      (node (ref "R237") (pin "1") (pinfunction "1_1") (pintype "passive"))
    )
    (net (code "62") (name "Net-(DD5-D6)") (class "Default")
      (node (ref "DD5") (pin "5") (pinfunction "D6_5") (pintype "passive"))
      (node (ref "R243") (pin "1") (pinfunction "1_1") (pintype "passive"))
    )
    (net (code "63") (name "Net-(DD5-D7)") (class "Default")
      (node (ref "DD5") (pin "6") (pinfunction "D7_6") (pintype "passive"))
      (node (ref "R238") (pin "1") (pinfunction "1_1") (pintype "passive"))
    )
    (net (code "64") (name "Net-(DD5-DS)") (class "Default")
      (node (ref "DD5") (pin "10") (pinfunction "DS_10") (pintype "passive"))
      (node (ref "R234") (pin "1") (pinfunction "1_1") (pintype "passive"))
    )
    (net (code "65") (name "Net-(DD5-Q7)") (class "Default")
      (node (ref "DD5") (pin "9") (pinfunction "Q7_9") (pintype "passive"))
      (node (ref "R239") (pin "1") (pinfunction "1_1") (pintype "passive"))
    )
    (net (code "66") (name "Net-(DD6-D0)") (class "Default")
      (node (ref "DD6") (pin "11") (pinfunction "D0_11") (pintype "passive"))
      (node (ref "R252") (pin "1") (pinfunction "1_1") (pintype "passive"))
    )
    (net (code "67") (name "Net-(DD6-D1)") (class "Default")
      (node (ref "DD6") (pin "12") (pinfunction "D1_12") (pintype "passive"))
      (node (ref "R247") (pin "1") (pinfunction "1_1") (pintype "passive"))
    )
    (net (code "68") (name "Net-(DD6-D2)") (class "Default")
      (node (ref "DD6") (pin "13") (pinfunction "D2_13") (pintype "passive"))
      (node (ref "R253") (pin "1") (pinfunction "1_1") (pintype "passive"))
    )
    (net (code "69") (name "Net-(DD6-D3)") (class "Default")
      (node (ref "DD6") (pin "14") (pinfunction "D3_14") (pintype "passive"))
      (node (ref "R248") (pin "1") (pinfunction "1_1") (pintype "passive"))
    )
    (net (code "70") (name "Net-(DD6-D4)") (class "Default")
      (node (ref "DD6") (pin "3") (pinfunction "D4_3") (pintype "passive"))
      (node (ref "R254") (pin "1") (pinfunction "1_1") (pintype "passive"))
    )
    (net (code "71") (name "Net-(DD6-D5)") (class "Default")
      (node (ref "DD6") (pin "4") (pinfunction "D5_4") (pintype "passive"))
      (node (ref "R249") (pin "1") (pinfunction "1_1") (pintype "passive"))
    )
    (net (code "72") (name "Net-(DD6-D6)") (class "Default")
      (node (ref "DD6") (pin "5") (pinfunction "D6_5") (pintype "passive"))
      (node (ref "R255") (pin "1") (pinfunction "1_1") (pintype "passive"))
    )
    (net (code "73") (name "Net-(DD6-D7)") (class "Default")
      (node (ref "DD6") (pin "6") (pinfunction "D7_6") (pintype "passive"))
      (node (ref "R250") (pin "1") (pinfunction "1_1") (pintype "passive"))
    )
    (net (code "74") (name "Net-(DD6-DS)") (class "Default")
      (node (ref "DD6") (pin "10") (pinfunction "DS_10") (pintype "passive"))
      (node (ref "R246") (pin "1") (pinfunction "1_1") (pintype "passive"))
    )
    (net (code "75") (name "Net-(DD6-Q7)") (class "Default")
      (node (ref "DD6") (pin "9") (pinfunction "Q7_9") (pintype "passive"))
      (node (ref "R251") (pin "1") (pinfunction "1_1") (pintype "passive"))
    )
    (net (code "76") (name "Net-(DD7-D0)") (class "Default")
      (node (ref "DD7") (pin "11") (pinfunction "D0_11") (pintype "passive"))
      (node (ref "R262") (pin "1") (pinfunction "1_1") (pintype "passive"))
    )
    (net (code "77") (name "Net-(DD7-D1)") (class "Default")
      (node (ref "DD7") (pin "12") (pinfunction "D1_12") (pintype "passive"))
      (node (ref "R257") (pin "1") (pinfunction "1_1") (pintype "passive"))
    )
    (net (code "78") (name "Net-(DD7-D2)") (class "Default")
      (node (ref "DD7") (pin "13") (pinfunction "D2_13") (pintype "passive"))
      (node (ref "R263") (pin "1") (pinfunction "1_1") (pintype "passive"))
    )
    (net (code "79") (name "Net-(DD7-D3)") (class "Default")
      (node (ref "DD7") (pin "14") (pinfunction "D3_14") (pintype "passive"))
      (node (ref "R258") (pin "1") (pinfunction "1_1") (pintype "passive"))
    )
    (net (code "80") (name "Net-(DD7-D4)") (class "Default")
      (node (ref "DD7") (pin "3") (pinfunction "D4_3") (pintype "passive"))
      (node (ref "R264") (pin "1") (pinfunction "1_1") (pintype "passive"))
    )
    (net (code "81") (name "Net-(DD7-D5)") (class "Default")
      (node (ref "DD7") (pin "4") (pinfunction "D5_4") (pintype "passive"))
      (node (ref "R259") (pin "1") (pinfunction "1_1") (pintype "passive"))
    )
    (net (code "82") (name "Net-(DD7-D6)") (class "Default")
      (node (ref "DD7") (pin "5") (pinfunction "D6_5") (pintype "passive"))
      (node (ref "R265") (pin "1") (pinfunction "1_1") (pintype "passive"))
    )
    (net (code "83") (name "Net-(DD7-D7)") (class "Default")
      (node (ref "DD7") (pin "6") (pinfunction "D7_6") (pintype "passive"))
      (node (ref "R260") (pin "1") (pinfunction "1_1") (pintype "passive"))
    )
    (net (code "84") (name "Net-(DD7-DS)") (class "Default")
      (node (ref "DD7") (pin "10") (pinfunction "DS_10") (pintype "passive"))
      (node (ref "R256") (pin "1") (pinfunction "1_1") (pintype "passive"))
    )
    (net (code "85") (name "Net-(DD7-Q7)") (class "Default")
      (node (ref "DD7") (pin "9") (pinfunction "Q7_9") (pintype "passive"))
      (node (ref "R261") (pin "1") (pinfunction "1_1") (pintype "passive"))
    )
    (net (code "86") (name "Net-(DD8-D0)") (class "Default")
      (node (ref "DD8") (pin "11") (pinfunction "D0_11") (pintype "passive"))
      (node (ref "R271") (pin "1") (pinfunction "1_1") (pintype "passive"))
    )
    (net (code "87") (name "Net-(DD8-D1)") (class "Default")
      (node (ref "DD8") (pin "12") (pinfunction "D1_12") (pintype "passive"))
      (node (ref "R270") (pin "1") (pinfunction "1_1") (pintype "passive"))
    )
    (net (code "88") (name "Net-(DD8-D2)") (class "Default")
      (node (ref "DD8") (pin "13") (pinfunction "D2_13") (pintype "passive"))
      (node (ref "R272") (pin "1") (pinfunction "1_1") (pintype "passive"))
    )
    (net (code "89") (name "Net-(DD8-D3)") (class "Default")
      (node (ref "DD8") (pin "14") (pinfunction "D3_14") (pintype "passive"))
      (node (ref "R266") (pin "1") (pinfunction "1_1") (pintype "passive"))
    )
    (net (code "90") (name "Net-(DD8-D4)") (class "Default")
      (node (ref "DD8") (pin "3") (pinfunction "D4_3") (pintype "passive"))
      (node (ref "R273") (pin "1") (pinfunction "1_1") (pintype "passive"))
    )
    (net (code "91") (name "Net-(DD8-D5)") (class "Default")
      (node (ref "DD8") (pin "4") (pinfunction "D5_4") (pintype "passive"))
      (node (ref "R267") (pin "1") (pinfunction "1_1") (pintype "passive"))
    )
    (net (code "92") (name "Net-(DD8-D6)") (class "Default")
      (node (ref "DD8") (pin "5") (pinfunction "D6_5") (pintype "passive"))
      (node (ref "R274") (pin "1") (pinfunction "1_1") (pintype "passive"))
    )
    (net (code "93") (name "Net-(DD8-D7)") (class "Default")
      (node (ref "DD8") (pin "6") (pinfunction "D7_6") (pintype "passive"))
      (node (ref "R268") (pin "1") (pinfunction "1_1") (pintype "passive"))
    )
    (net (code "94") (name "Net-(DD8-DS)") (class "Default")
      (node (ref "DD8") (pin "10") (pinfunction "DS_10") (pintype "passive"))
      (node (ref "R269") (pin "1") (pinfunction "1_1") (pintype "passive"))
    )
    (net (code "95") (name "Net-(R226-Pad2)") (class "Default")
      (node (ref "R226") (pin "2") (pinfunction "2_2") (pintype "passive"))
      (node (ref "R234") (pin "2") (pinfunction "2_2") (pintype "passive"))
    )
    (net (code "96") (name "Net-(R239-Pad2)") (class "Default")
      (node (ref "R239") (pin "2") (pinfunction "2_2") (pintype "passive"))
      (node (ref "R246") (pin "2") (pinfunction "2_2") (pintype "passive"))
    )
    (net (code "97") (name "Net-(R251-Pad2)") (class "Default")
      (node (ref "R251") (pin "2") (pinfunction "2_2") (pintype "passive"))
      (node (ref "R256") (pin "2") (pinfunction "2_2") (pintype "passive"))
    )
    (net (code "98") (name "Net-(R261-Pad2)") (class "Default")
      (node (ref "R261") (pin "2") (pinfunction "2_2") (pintype "passive"))
      (node (ref "R269") (pin "2") (pinfunction "2_2") (pintype "passive"))
    )
    (net (code "99") (name "unconnected-(DD4-DS-Pad10)") (class "Default")
      (node (ref "DD4") (pin "10") (pinfunction "DS_10") (pintype "passive+no_connect"))
    )
    (net (code "100") (name "unconnected-(DD4-~{Q7}-Pad7)") (class "Default")
      (node (ref "DD4") (pin "7") (pinfunction "~{Q7}_7") (pintype "passive+no_connect"))
    )
    (net (code "101") (name "unconnected-(DD5-~{Q7}-Pad7)") (class "Default")
      (node (ref "DD5") (pin "7") (pinfunction "~{Q7}_7") (pintype "passive+no_connect"))
    )
    (net (code "102") (name "unconnected-(DD6-~{Q7}-Pad7)") (class "Default")
      (node (ref "DD6") (pin "7") (pinfunction "~{Q7}_7") (pintype "passive+no_connect"))
    )
    (net (code "103") (name "unconnected-(DD7-~{Q7}-Pad7)") (class "Default")
      (node (ref "DD7") (pin "7") (pinfunction "~{Q7}_7") (pintype "passive+no_connect"))
    )
    (net (code "104") (name "unconnected-(DD8-~{Q7}-Pad7)") (class "Default")
      (node (ref "DD8") (pin "7") (pinfunction "~{Q7}_7") (pintype "passive+no_connect"))
    )
  )
)
